# SunS_Decoupler.net
KiCad netlist of a schematic drawn in Altium Designer
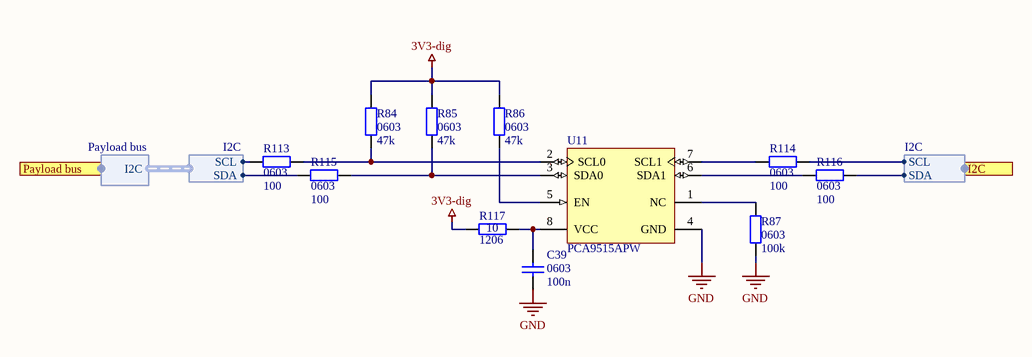
[diagram p0: SunS_Decoupler.SchDoc]

(export (version "E")
  (design (tool "Eeschema 10.0.6"))
  (components
    (comp (ref "C39")
      (value "0603")
      (footprint "SMD_Capacitor_0603")
      (description "Capacitor")
      (fields (field (name "ALTIUM_VALUE") "100n") (field (name "PUBLISHER") "Altium Limited"))
      (libsource (lib "Miscellaneous Devices") (part "Cap"))
    )
    (comp (ref "R84")
      (value "0603")
      (footprint "SMD_Resistor_0603")
      (description "Resistor")
      (fields (field (name "ALTIUM_VALUE") "47k") (field (name "PUBLISHER") "Altium Limited"))
      (libsource (lib "") (part "Res2_1"))
    )
    (comp (ref "R85")
      (value "0603")
      (footprint "SMD_Resistor_0603")
      (description "Resistor")
      (fields (field (name "ALTIUM_VALUE") "47k") (field (name "PUBLISHER") "Altium Limited"))
      (libsource (lib "") (part "Res2_1"))
    )
    (comp (ref "R86")
      (value "0603")
      (footprint "SMD_Resistor_0603")
      (description "Resistor")
      (fields (field (name "ALTIUM_VALUE") "47k") (field (name "PUBLISHER") "Altium Limited"))
      (libsource (lib "") (part "Res2_1"))
    )
    (comp (ref "R87")
      (value "0603")
      (footprint "SMD_Resistor_0603")
      (description "Resistor")
      (fields (field (name "ALTIUM_VALUE") "100k") (field (name "PUBLISHER") "Altium Limited"))
      (libsource (lib "") (part "Res2_1"))
    )
    (comp (ref "R113")
      (value "0603")
      (footprint "SMD_Resistor_0603")
      (description "Resistor")
      (fields (field (name "ALTIUM_VALUE") "100") (field (name "PUBLISHER") "Altium Limited"))
      (libsource (lib "Miscellaneous Devices") (part "Res2"))
    )
    (comp (ref "R114")
      (value "0603")
      (footprint "SMD_Resistor_0603")
      (description "Resistor")
      (fields (field (name "ALTIUM_VALUE") "100") (field (name "PUBLISHER") "Altium Limited"))
      (libsource (lib "Miscellaneous Devices") (part "Res2"))
    )
    (comp (ref "R115")
      (value "0603")
      (footprint "SMD_Resistor_0603")
      (description "Resistor")
      (fields (field (name "ALTIUM_VALUE") "100") (field (name "PUBLISHER") "Altium Limited"))
      (libsource (lib "Miscellaneous Devices") (part "Res2"))
    )
    (comp (ref "R116")
      (value "0603")
      (footprint "SMD_Resistor_0603")
      (description "Resistor")
      (fields (field (name "ALTIUM_VALUE") "100") (field (name "PUBLISHER") "Altium Limited"))
      (libsource (lib "Miscellaneous Devices") (part "Res2"))
    )
    (comp (ref "R117")
      (value "1206")
      (footprint "SMD_Resistor_1206")
      (description "Resistor")
      (fields (field (name "ALTIUM_VALUE") "10") (field (name "PUBLISHER") "Altium Limited"))
      (libsource (lib "Miscellaneous Devices") (part "Res2"))
    )
    (comp (ref "U11")
      (value "PCA9515APW")
      (footprint "PW8_L")
      (fields (field (name "MANUFACTURER") "Texas Instruments"))
      (libsource (lib "microcircuits_miscellaneous") (part "PCA9515APW"))
    )
  )
  (nets
    (net (code "7") (name "3V3-dig") (class "Default")
      (node (ref "R117") (pin "2") (pinfunction "2_2") (pintype "passive"))
      (node (ref "R84") (pin "2") (pinfunction "2_2") (pintype "passive"))
      (node (ref "R85") (pin "2") (pinfunction "2_2") (pintype "passive"))
      (node (ref "R86") (pin "2") (pinfunction "2_2") (pintype "passive"))
    )
    (net (code "8") (name "GND") (class "Default")
      (node (ref "C39") (pin "1") (pinfunction "1_1") (pintype "passive"))
      (node (ref "R87") (pin "1") (pinfunction "1_1") (pintype "passive"))
      (node (ref "U11") (pin "4") (pinfunction "GND_4") (pintype "power_in"))
    )
    (net (code "9") (name "Net-(U11-EN)") (class "Default")
      (node (ref "R86") (pin "1") (pinfunction "1_1") (pintype "passive"))
      (node (ref "U11") (pin "5") (pinfunction "EN_5") (pintype "input"))
    )
    (net (code "10") (name "Net-(U11-NC)") (class "Default")
      (node (ref "R87") (pin "2") (pinfunction "2_2") (pintype "passive"))
      (node (ref "U11") (pin "1") (pinfunction "NC_1") (pintype "passive"))
    )
    (net (code "11") (name "Net-(U11-SCL0)") (class "Default")
      (node (ref "R113") (pin "1") (pinfunction "1_1") (pintype "passive"))
      (node (ref "R84") (pin "1") (pinfunction "1_1") (pintype "passive"))
      (node (ref "U11") (pin "2") (pinfunction "SCL0_2") (pintype "bidirectional"))
    )
    (net (code "12") (name "Net-(U11-SCL1)") (class "Default")
      (node (ref "R114") (pin "2") (pinfunction "2_2") (pintype "passive"))
      (node (ref "U11") (pin "7") (pinfunction "SCL1_7") (pintype "bidirectional"))
    )
    (net (code "13") (name "Net-(U11-SDA0)") (class "Default")
      (node (ref "R115") (pin "1") (pinfunction "1_1") (pintype "passive"))
      (node (ref "R85") (pin "1") (pinfunction "1_1") (pintype "passive"))
      (node (ref "U11") (pin "3") (pinfunction "SDA0_3") (pintype "bidirectional"))
    )
    (net (code "14") (name "Net-(U11-SDA1)") (class "Default")
      (node (ref "R116") (pin "2") (pinfunction "2_2") (pintype "passive"))
      (node (ref "U11") (pin "6") (pinfunction "SDA1_6") (pintype "bidirectional"))
    )
    (net (code "15") (name "Net-(U11-VCC)") (class "Default")
      (node (ref "C39") (pin "2") (pinfunction "2_2") (pintype "passive"))
      (node (ref "R117") (pin "1") (pinfunction "1_1") (pintype "passive"))
      (node (ref "U11") (pin "8") (pinfunction "VCC_8") (pintype "power_in"))
    )
    (net (code "16") (name "unconnected-(R113-Pad2)") (class "Default")
      (node (ref "R113") (pin "2") (pinfunction "2_2") (pintype "passive"))
    )
    (net (code "17") (name "unconnected-(R114-Pad1)") (class "Default")
      (node (ref "R114") (pin "1") (pinfunction "1_1") (pintype "passive"))
    )
    (net (code "18") (name "unconnected-(R115-Pad2)") (class "Default")
      (node (ref "R115") (pin "2") (pinfunction "2_2") (pintype "passive"))
    )
    (net (code "19") (name "unconnected-(R116-Pad1)") (class "Default")
      (node (ref "R116") (pin "1") (pinfunction "1_1") (pintype "passive"))
    )
  )
)
